# ESD_Protector.net
KiCad netlist of a schematic drawn in Altium Designer
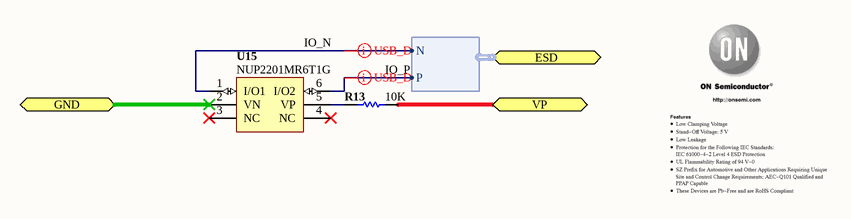
[diagram p0: ESD_Protector.SchDoc]

(export (version "E")
  (design (tool "Eeschema 10.0.6"))
  (components
    (comp (ref "R13")
      (value "10K")
      (footprint "RESC0402(1005)_N")
      (description "10K 0.063W 1% 0402 (1005 Metric)  SMD")
      (fields (field (name "TOLERANCE") "1 %") (field (name "POWER") "0.063 W"))
      (libsource (lib "Altium Content Vault") (part "CMP-1011-00623-1"))
    )
    (comp (ref "U15")
      (value "NUP2201MR6T1G")
      (footprint "ONSC-318G-02")
      (description "IC TVS DIODE ARRAY HS LINE 6TSOP")
      (libsource (lib "Altium Content Vault") (part "CMP-5150-00000-1"))
    )
  )
  (nets
    (net (code "2") (name "/GND") (class "Default")
      (node (ref "U15") (pin "2") (pinfunction "VN_2") (pintype "power_in+no_connect"))
    )
    (net (code "3") (name "/IO_N") (class "Default")
      (node (ref "U15") (pin "1") (pinfunction "I/O1_1") (pintype "bidirectional"))
    )
    (net (code "4") (name "/IO_P") (class "Default")
      (node (ref "U15") (pin "6") (pinfunction "I/O2_6") (pintype "bidirectional"))
    )
    (net (code "5") (name "/VP") (class "Default")
      (node (ref "R13") (pin "1") (pinfunction "1_1") (pintype "passive"))
    )
    (net (code "7") (name "Net-(U15-VP)") (class "Default")
      (node (ref "R13") (pin "2") (pinfunction "2_2") (pintype "passive"))
      (node (ref "U15") (pin "5") (pinfunction "VP_5") (pintype "power_in"))
    )
    (net (code "8") (name "unconnected-(U15-NC-Pad3)") (class "Default")
      (node (ref "U15") (pin "3") (pinfunction "NC_3") (pintype "passive+no_connect"))
    )
    (net (code "9") (name "unconnected-(U15-NC-Pad4)") (class "Default")
      (node (ref "U15") (pin "4") (pinfunction "NC_4") (pintype "passive+no_connect"))
    )
  )
)
